# solar_mains_charge_manager.net
KiCad netlist of a schematic drawn in EAGLE
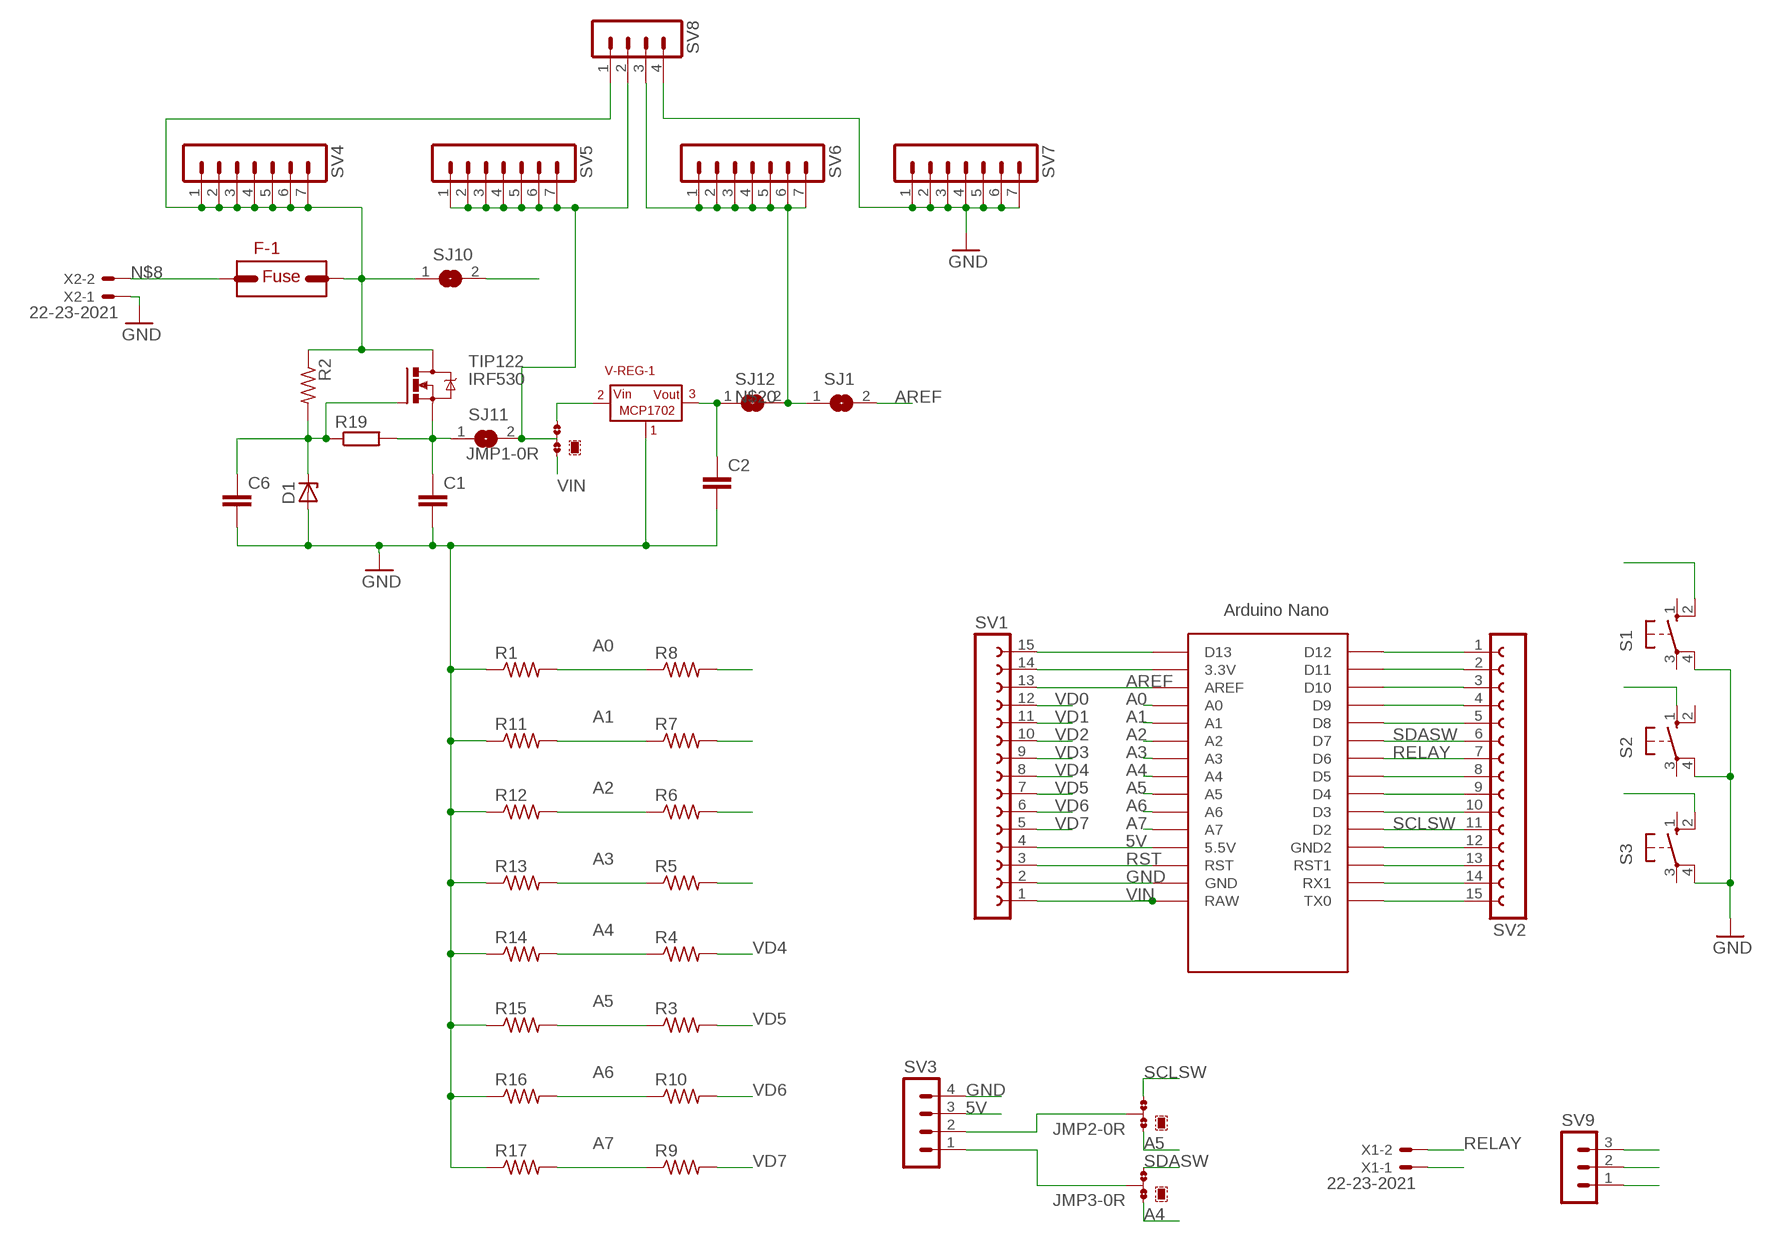
[diagram p0: schematic, sheet 1]

(export (version "E")
  (design (tool "Eeschema 10.0.6"))
  (components
    (comp (ref "C1")
      (value "C2,5-3")
      (footprint "eagle-import:C2.5-3")
      (libsource (lib "eagle-import") (part "C2,5-3"))
    )
    (comp (ref "C2")
      (value "C2,5-3")
      (footprint "eagle-import:C2.5-3")
      (libsource (lib "eagle-import") (part "C2,5-3"))
    )
    (comp (ref "C6")
      (value "C2,5-3")
      (footprint "eagle-import:C2.5-3")
      (libsource (lib "eagle-import") (part "C2,5-3"))
    )
    (comp (ref "D1")
      (value "ZENER-DIODEDO34-7")
      (footprint "eagle-import:DO34Z7")
      (libsource (lib "eagle-import") (part "ZENER-DIODEDO34-7"))
    )
    (comp (ref "F-1")
      (value "FUSE")
      (footprint "eagle-import:FUSE")
      (libsource (lib "eagle-import") (part "FUSE"))
    )
    (comp (ref "JMP1")
      (value "0R-JUMPA")
      (footprint "eagle-import:A0R-JMP")
      (libsource (lib "eagle-import") (part "0R-JUMPA"))
    )
    (comp (ref "JMP2")
      (value "0R-JUMPA")
      (footprint "eagle-import:A0R-JMP")
      (libsource (lib "eagle-import") (part "0R-JUMPA"))
    )
    (comp (ref "JMP3")
      (value "0R-JUMPA")
      (footprint "eagle-import:A0R-JMP")
      (libsource (lib "eagle-import") (part "0R-JUMPA"))
    )
    (comp (ref "R1")
      (value "R-US_0204/5")
      (footprint "eagle-import:0204_5")
      (libsource (lib "eagle-import") (part "R-US_0204/5"))
    )
    (comp (ref "R2")
      (value "R-US_0204/2V")
      (footprint "eagle-import:0204V")
      (libsource (lib "eagle-import") (part "resistor_348_R-US_0204/2V"))
    )
    (comp (ref "R3")
      (value "R-US_0204/2V")
      (footprint "eagle-import:0204V")
      (libsource (lib "eagle-import") (part "resistor_348_R-US_0204/2V"))
    )
    (comp (ref "R4")
      (value "R-US_0204/2V")
      (footprint "eagle-import:0204V")
      (libsource (lib "eagle-import") (part "resistor_348_R-US_0204/2V"))
    )
    (comp (ref "R5")
      (value "R-US_0204/2V")
      (footprint "eagle-import:0204V")
      (libsource (lib "eagle-import") (part "resistor_348_R-US_0204/2V"))
    )
    (comp (ref "R6")
      (value "R-US_0204/2V")
      (footprint "eagle-import:0204V")
      (libsource (lib "eagle-import") (part "resistor_348_R-US_0204/2V"))
    )
    (comp (ref "R7")
      (value "R-US_0204/2V")
      (footprint "eagle-import:0204V")
      (libsource (lib "eagle-import") (part "resistor_348_R-US_0204/2V"))
    )
    (comp (ref "R8")
      (value "R-US_0204/2V")
      (footprint "eagle-import:0204V")
      (libsource (lib "eagle-import") (part "resistor_348_R-US_0204/2V"))
    )
    (comp (ref "R9")
      (value "R-US_0204/2V")
      (footprint "eagle-import:0204V")
      (libsource (lib "eagle-import") (part "resistor_348_R-US_0204/2V"))
    )
    (comp (ref "R10")
      (value "R-US_0204/2V")
      (footprint "eagle-import:0204V")
      (libsource (lib "eagle-import") (part "resistor_348_R-US_0204/2V"))
    )
    (comp (ref "R11")
      (value "R-US_0204/5")
      (footprint "eagle-import:0204_5")
      (libsource (lib "eagle-import") (part "R-US_0204/5"))
    )
    (comp (ref "R12")
      (value "R-US_0204/5")
      (footprint "eagle-import:0204_5")
      (libsource (lib "eagle-import") (part "R-US_0204/5"))
    )
    (comp (ref "R13")
      (value "R-US_0204/5")
      (footprint "eagle-import:0204_5")
      (libsource (lib "eagle-import") (part "R-US_0204/5"))
    )
    (comp (ref "R14")
      (value "R-US_0204/5")
      (footprint "eagle-import:0204_5")
      (libsource (lib "eagle-import") (part "R-US_0204/5"))
    )
    (comp (ref "R15")
      (value "R-US_0204/5")
      (footprint "eagle-import:0204_5")
      (libsource (lib "eagle-import") (part "R-US_0204/5"))
    )
    (comp (ref "R16")
      (value "R-US_0204/5")
      (footprint "eagle-import:0204_5")
      (libsource (lib "eagle-import") (part "R-US_0204/5"))
    )
    (comp (ref "R17")
      (value "R-US_0204/5")
      (footprint "eagle-import:0204_5")
      (libsource (lib "eagle-import") (part "R-US_0204/5"))
    )
    (comp (ref "R19")
      (value "R-EU_0204/5")
      (footprint "eagle-import:0204_5")
      (libsource (lib "eagle-import") (part "R-EU_0204/5"))
    )
    (comp (ref "S1")
      (value "10-XX")
      (footprint "eagle-import:B3F-10XX")
      (fields (field (name "MPN") "B3F-1000"))
      (libsource (lib "eagle-import") (part "10-XX"))
    )
    (comp (ref "S2")
      (value "10-XX")
      (footprint "eagle-import:B3F-10XX")
      (fields (field (name "MPN") "B3F-1000"))
      (libsource (lib "eagle-import") (part "10-XX"))
    )
    (comp (ref "S3")
      (value "10-XX")
      (footprint "eagle-import:B3F-10XX")
      (fields (field (name "MPN") "B3F-1000"))
      (libsource (lib "eagle-import") (part "10-XX"))
    )
    (comp (ref "SJ1") (value "SJ") (footprint "eagle-import:SJ") (libsource (lib "eagle-import") (part "SJ")))
    (comp (ref "SJ10")
      (value "SJ")
      (footprint "eagle-import:SJ")
      (libsource (lib "eagle-import") (part "SJ"))
    )
    (comp (ref "SJ11")
      (value "SJ")
      (footprint "eagle-import:SJ")
      (libsource (lib "eagle-import") (part "SJ"))
    )
    (comp (ref "SJ12")
      (value "SJ")
      (footprint "eagle-import:SJ")
      (libsource (lib "eagle-import") (part "SJ"))
    )
    (comp (ref "SV1")
      (value "FE15-1")
      (footprint "eagle-import:FE15")
      (libsource (lib "eagle-import") (part "FE15-1"))
    )
    (comp (ref "SV2")
      (value "FE15-1")
      (footprint "eagle-import:FE15")
      (libsource (lib "eagle-import") (part "FE15-1"))
    )
    (comp (ref "SV3")
      (value "MA04-1")
      (footprint "eagle-import:MA04-1")
      (libsource (lib "eagle-import") (part "MA04-1"))
    )
    (comp (ref "SV4")
      (value "MA07-1")
      (footprint "eagle-import:MA07-1")
      (libsource (lib "eagle-import") (part "MA07-1"))
    )
    (comp (ref "SV5")
      (value "MA07-1")
      (footprint "eagle-import:MA07-1")
      (libsource (lib "eagle-import") (part "MA07-1"))
    )
    (comp (ref "SV6")
      (value "MA07-1")
      (footprint "eagle-import:MA07-1")
      (libsource (lib "eagle-import") (part "MA07-1"))
    )
    (comp (ref "SV7")
      (value "MA07-1")
      (footprint "eagle-import:MA07-1")
      (libsource (lib "eagle-import") (part "MA07-1"))
    )
    (comp (ref "SV8")
      (value "MA04-1")
      (footprint "eagle-import:MA04-1")
      (libsource (lib "eagle-import") (part "MA04-1"))
    )
    (comp (ref "SV9")
      (value "MA03-1")
      (footprint "eagle-import:MA03-1")
      (libsource (lib "eagle-import") (part "MA03-1"))
    )
    (comp (ref "TIP122")
      (value "IRF530")
      (footprint "eagle-import:TO220BV")
      (libsource (lib "eagle-import") (part "IRF530"))
    )
    (comp (ref "U$1")
      (value "NANO")
      (footprint "eagle-import:NANO")
      (libsource (lib "eagle-import") (part "NANO"))
    )
    (comp (ref "V-REG-1")
      (value "MCP1702")
      (footprint "eagle-import:TO92")
      (libsource (lib "eagle-import") (part "MCP1702"))
    )
    (comp (ref "X1")
      (value "22-23-2021")
      (footprint "eagle-import:22-23-2021")
      (fields (field (name "MF") "MOLEX"))
      (libsource (lib "eagle-import") (part "22-23-2021"))
    )
    (comp (ref "X2")
      (value "22-23-2021")
      (footprint "eagle-import:22-23-2021")
      (fields (field (name "MF") "MOLEX"))
      (libsource (lib "eagle-import") (part "22-23-2021"))
    )
  )
  (nets
    (net (code "1") (name "/5V") (class "Default")
      (node (ref "SJ1") (pin "1") (pinfunction "1_1") (pintype "passive"))
      (node (ref "SJ12") (pin "2") (pinfunction "2_2") (pintype "passive"))
      (node (ref "SV1") (pin "4") (pinfunction "4_4") (pintype "passive"))
      (node (ref "SV3") (pin "3") (pinfunction "3_3") (pintype "passive"))
      (node (ref "SV6") (pin "1") (pinfunction "1_1") (pintype "passive"))
      (node (ref "SV6") (pin "2") (pinfunction "2_2") (pintype "passive"))
      (node (ref "SV6") (pin "3") (pinfunction "3_3") (pintype "passive"))
      (node (ref "SV6") (pin "4") (pinfunction "4_4") (pintype "passive"))
      (node (ref "SV6") (pin "5") (pinfunction "5_5") (pintype "passive"))
      (node (ref "SV6") (pin "6") (pinfunction "6_6") (pintype "passive"))
      (node (ref "SV6") (pin "7") (pinfunction "7_7") (pintype "passive"))
      (node (ref "SV8") (pin "3") (pinfunction "3_3") (pintype "passive"))
      (node (ref "SV9") (pin "3") (pinfunction "3_3") (pintype "passive"))
      (node (ref "U$1") (pin "5V") (pinfunction "5.5V_5V") (pintype "bidirectional"))
    )
    (net (code "2") (name "/A0") (class "Default")
      (node (ref "R1") (pin "2") (pinfunction "2_2") (pintype "passive"))
      (node (ref "R8") (pin "1") (pinfunction "1_1") (pintype "passive"))
      (node (ref "U$1") (pin "A0") (pinfunction "A0_A0") (pintype "bidirectional"))
    )
    (net (code "3") (name "/A1") (class "Default")
      (node (ref "R11") (pin "2") (pinfunction "2_2") (pintype "passive"))
      (node (ref "R7") (pin "1") (pinfunction "1_1") (pintype "passive"))
      (node (ref "U$1") (pin "A1") (pinfunction "A1_A1") (pintype "bidirectional"))
    )
    (net (code "4") (name "/A2") (class "Default")
      (node (ref "R12") (pin "2") (pinfunction "2_2") (pintype "passive"))
      (node (ref "R6") (pin "1") (pinfunction "1_1") (pintype "passive"))
      (node (ref "U$1") (pin "A2") (pinfunction "A2_A2") (pintype "bidirectional"))
    )
    (net (code "5") (name "/A3") (class "Default")
      (node (ref "R13") (pin "2") (pinfunction "2_2") (pintype "passive"))
      (node (ref "R5") (pin "1") (pinfunction "1_1") (pintype "passive"))
      (node (ref "U$1") (pin "A3") (pinfunction "A3_A3") (pintype "bidirectional"))
    )
    (net (code "6") (name "/A4") (class "Default")
      (node (ref "JMP3") (pin "1") (pinfunction "1_1") (pintype "passive"))
      (node (ref "R14") (pin "2") (pinfunction "2_2") (pintype "passive"))
      (node (ref "R4") (pin "1") (pinfunction "1_1") (pintype "passive"))
      (node (ref "U$1") (pin "A4") (pinfunction "A4_A4") (pintype "bidirectional"))
    )
    (net (code "7") (name "/A5") (class "Default")
      (node (ref "JMP2") (pin "1") (pinfunction "1_1") (pintype "passive"))
      (node (ref "R15") (pin "2") (pinfunction "2_2") (pintype "passive"))
      (node (ref "R3") (pin "1") (pinfunction "1_1") (pintype "passive"))
      (node (ref "U$1") (pin "A5") (pinfunction "A5_A5") (pintype "bidirectional"))
    )
    (net (code "8") (name "/A6") (class "Default")
      (node (ref "R10") (pin "1") (pinfunction "1_1") (pintype "passive"))
      (node (ref "R16") (pin "2") (pinfunction "2_2") (pintype "passive"))
      (node (ref "U$1") (pin "A6") (pinfunction "A6_A6") (pintype "bidirectional"))
    )
    (net (code "9") (name "/A7") (class "Default")
      (node (ref "R17") (pin "2") (pinfunction "2_2") (pintype "passive"))
      (node (ref "R9") (pin "1") (pinfunction "1_1") (pintype "passive"))
      (node (ref "SV9") (pin "1") (pinfunction "1_1") (pintype "passive"))
      (node (ref "U$1") (pin "A7") (pinfunction "A7_A7") (pintype "bidirectional"))
    )
    (net (code "10") (name "/AREF") (class "Default")
      (node (ref "SJ1") (pin "2") (pinfunction "2_2") (pintype "passive"))
      (node (ref "SV1") (pin "13") (pinfunction "13_13") (pintype "passive"))
      (node (ref "U$1") (pin "AREF") (pinfunction "AREF_AREF") (pintype "bidirectional"))
    )
    (net (code "11") (name "/D8") (class "Default")
      (node (ref "S2") (pin "1") (pinfunction "S_1") (pintype "passive"))
      (node (ref "SV2") (pin "5") (pinfunction "5_5") (pintype "passive"))
      (node (ref "U$1") (pin "D8") (pinfunction "D8_D8") (pintype "bidirectional"))
    )
    (net (code "12") (name "/D9") (class "Default")
      (node (ref "S1") (pin "2") (pinfunction "S1_2") (pintype "passive"))
      (node (ref "SV2") (pin "4") (pinfunction "4_4") (pintype "passive"))
      (node (ref "U$1") (pin "D9") (pinfunction "D9_D9") (pintype "bidirectional"))
    )
    (net (code "13") (name "/N$8") (class "Default")
      (node (ref "F-1") (pin "P$1") (pinfunction "P$1_P$1") (pintype "passive"))
      (node (ref "X2") (pin "2") (pinfunction "S_2") (pintype "passive"))
    )
    (net (code "14") (name "/N$20") (class "Default")
      (node (ref "C2") (pin "1") (pinfunction "1_1") (pintype "passive"))
      (node (ref "SJ12") (pin "1") (pinfunction "1_1") (pintype "passive"))
      (node (ref "V-REG-1") (pin "3") (pinfunction "P$3_3") (pintype "power_in"))
    )
    (net (code "15") (name "/RELAY") (class "Default")
      (node (ref "SV2") (pin "7") (pinfunction "7_7") (pintype "passive"))
      (node (ref "U$1") (pin "D6") (pinfunction "D6_D6") (pintype "bidirectional"))
      (node (ref "X1") (pin "2") (pinfunction "S_2") (pintype "passive"))
    )
    (net (code "16") (name "/RST") (class "Default")
      (node (ref "S3") (pin "2") (pinfunction "S1_2") (pintype "passive"))
      (node (ref "SV1") (pin "3") (pinfunction "3_3") (pintype "passive"))
      (node (ref "U$1") (pin "RST") (pinfunction "RST_RST") (pintype "bidirectional"))
    )
    (net (code "17") (name "/SCLSW") (class "Default")
      (node (ref "JMP2") (pin "3") (pinfunction "3_3") (pintype "passive"))
      (node (ref "SV2") (pin "11") (pinfunction "11_11") (pintype "passive"))
      (node (ref "U$1") (pin "D2") (pinfunction "D2_D2") (pintype "bidirectional"))
    )
    (net (code "18") (name "/SDASW") (class "Default")
      (node (ref "JMP3") (pin "3") (pinfunction "3_3") (pintype "passive"))
      (node (ref "SV2") (pin "6") (pinfunction "6_6") (pintype "passive"))
      (node (ref "U$1") (pin "D7") (pinfunction "D7_D7") (pintype "bidirectional"))
    )
    (net (code "19") (name "/VD0") (class "Default")
      (node (ref "R8") (pin "2") (pinfunction "2_2") (pintype "passive"))
      (node (ref "SJ10") (pin "2") (pinfunction "2_2") (pintype "passive"))
      (node (ref "SV1") (pin "12") (pinfunction "12_12") (pintype "passive"))
    )
    (net (code "20") (name "/VD1") (class "Default")
      (node (ref "R7") (pin "2") (pinfunction "2_2") (pintype "passive"))
      (node (ref "SV1") (pin "11") (pinfunction "11_11") (pintype "passive"))
    )
    (net (code "21") (name "/VD2") (class "Default")
      (node (ref "R6") (pin "2") (pinfunction "2_2") (pintype "passive"))
      (node (ref "SV1") (pin "10") (pinfunction "10_10") (pintype "passive"))
    )
    (net (code "22") (name "/VD3") (class "Default")
      (node (ref "R5") (pin "2") (pinfunction "2_2") (pintype "passive"))
      (node (ref "SV1") (pin "9") (pinfunction "9_9") (pintype "passive"))
    )
    (net (code "23") (name "/VD4") (class "Default")
      (node (ref "R4") (pin "2") (pinfunction "2_2") (pintype "passive"))
      (node (ref "SV1") (pin "8") (pinfunction "8_8") (pintype "passive"))
    )
    (net (code "24") (name "/VD5") (class "Default")
      (node (ref "R3") (pin "2") (pinfunction "2_2") (pintype "passive"))
      (node (ref "SV1") (pin "7") (pinfunction "7_7") (pintype "passive"))
    )
    (net (code "25") (name "/VD6") (class "Default")
      (node (ref "R10") (pin "2") (pinfunction "2_2") (pintype "passive"))
      (node (ref "SV1") (pin "6") (pinfunction "6_6") (pintype "passive"))
    )
    (net (code "26") (name "/VD7") (class "Default")
      (node (ref "R9") (pin "2") (pinfunction "2_2") (pintype "passive"))
      (node (ref "SV1") (pin "5") (pinfunction "5_5") (pintype "passive"))
    )
    (net (code "27") (name "/VIN") (class "Default")
      (node (ref "JMP1") (pin "1") (pinfunction "1_1") (pintype "passive"))
      (node (ref "SV1") (pin "1") (pinfunction "1_1") (pintype "passive"))
      (node (ref "U$1") (pin "RAW") (pinfunction "RAW_RAW") (pintype "bidirectional"))
    )
    (net (code "28") (name "GND") (class "Default")
      (node (ref "C1") (pin "2") (pinfunction "2_2") (pintype "passive"))
      (node (ref "C2") (pin "2") (pinfunction "2_2") (pintype "passive"))
      (node (ref "C6") (pin "2") (pinfunction "2_2") (pintype "passive"))
      (node (ref "D1") (pin "A") (pinfunction "A_A") (pintype "passive"))
      (node (ref "R1") (pin "1") (pinfunction "1_1") (pintype "passive"))
      (node (ref "R11") (pin "1") (pinfunction "1_1") (pintype "passive"))
      (node (ref "R12") (pin "1") (pinfunction "1_1") (pintype "passive"))
      (node (ref "R13") (pin "1") (pinfunction "1_1") (pintype "passive"))
      (node (ref "R14") (pin "1") (pinfunction "1_1") (pintype "passive"))
      (node (ref "R15") (pin "1") (pinfunction "1_1") (pintype "passive"))
      (node (ref "R16") (pin "1") (pinfunction "1_1") (pintype "passive"))
      (node (ref "R17") (pin "1") (pinfunction "1_1") (pintype "passive"))
      (node (ref "S1") (pin "4") (pinfunction "P1_4") (pintype "passive"))
      (node (ref "S2") (pin "4") (pinfunction "P1_4") (pintype "passive"))
      (node (ref "S3") (pin "4") (pinfunction "P1_4") (pintype "passive"))
      (node (ref "SV1") (pin "2") (pinfunction "2_2") (pintype "passive"))
      (node (ref "SV2") (pin "12") (pinfunction "12_12") (pintype "passive"))
      (node (ref "SV3") (pin "4") (pinfunction "4_4") (pintype "passive"))
      (node (ref "SV7") (pin "1") (pinfunction "1_1") (pintype "passive"))
      (node (ref "SV7") (pin "2") (pinfunction "2_2") (pintype "passive"))
      (node (ref "SV7") (pin "3") (pinfunction "3_3") (pintype "passive"))
      (node (ref "SV7") (pin "4") (pinfunction "4_4") (pintype "passive"))
      (node (ref "SV7") (pin "5") (pinfunction "5_5") (pintype "passive"))
      (node (ref "SV7") (pin "6") (pinfunction "6_6") (pintype "passive"))
      (node (ref "SV7") (pin "7") (pinfunction "7_7") (pintype "passive"))
      (node (ref "SV8") (pin "4") (pinfunction "4_4") (pintype "passive"))
      (node (ref "SV9") (pin "2") (pinfunction "2_2") (pintype "passive"))
      (node (ref "U$1") (pin "GND") (pinfunction "GND_GND") (pintype "bidirectional"))
      (node (ref "U$1") (pin "GND1") (pinfunction "GND2_GND1") (pintype "bidirectional"))
      (node (ref "V-REG-1") (pin "1") (pinfunction "P$2_1") (pintype "power_in"))
      (node (ref "X1") (pin "1") (pinfunction "S_1") (pintype "passive"))
      (node (ref "X2") (pin "1") (pinfunction "S_1") (pintype "passive"))
    )
    (net (code "29") (name "Net-(C1-Pad1)") (class "Default")
      (node (ref "C1") (pin "1") (pinfunction "1_1") (pintype "passive"))
      (node (ref "R19") (pin "2") (pinfunction "2_2") (pintype "passive"))
      (node (ref "SJ11") (pin "1") (pinfunction "1_1") (pintype "passive"))
      (node (ref "TIP122") (pin "S") (pinfunction "S_S") (pintype "passive"))
    )
    (net (code "30") (name "Net-(C6-Pad1)") (class "Default")
      (node (ref "C6") (pin "1") (pinfunction "1_1") (pintype "passive"))
      (node (ref "D1") (pin "C") (pinfunction "C_C") (pintype "passive"))
      (node (ref "R19") (pin "1") (pinfunction "1_1") (pintype "passive"))
      (node (ref "R2") (pin "2") (pinfunction "2_2") (pintype "passive"))
      (node (ref "TIP122") (pin "G") (pinfunction "G_G") (pintype "passive"))
    )
    (net (code "31") (name "Net-(F-1-PadP$2)") (class "Default")
      (node (ref "F-1") (pin "P$2") (pinfunction "P$2_P$2") (pintype "passive"))
      (node (ref "R2") (pin "1") (pinfunction "1_1") (pintype "passive"))
      (node (ref "SJ10") (pin "1") (pinfunction "1_1") (pintype "passive"))
      (node (ref "SV4") (pin "1") (pinfunction "1_1") (pintype "passive"))
      (node (ref "SV4") (pin "2") (pinfunction "2_2") (pintype "passive"))
      (node (ref "SV4") (pin "3") (pinfunction "3_3") (pintype "passive"))
      (node (ref "SV4") (pin "4") (pinfunction "4_4") (pintype "passive"))
      (node (ref "SV4") (pin "5") (pinfunction "5_5") (pintype "passive"))
      (node (ref "SV4") (pin "6") (pinfunction "6_6") (pintype "passive"))
      (node (ref "SV4") (pin "7") (pinfunction "7_7") (pintype "passive"))
      (node (ref "SV8") (pin "1") (pinfunction "1_1") (pintype "passive"))
      (node (ref "TIP122") (pin "D") (pinfunction "D_D") (pintype "passive"))
    )
    (net (code "32") (name "Net-(JMP1-Pad2)") (class "Default")
      (node (ref "JMP1") (pin "2") (pinfunction "2_2") (pintype "passive"))
      (node (ref "SJ11") (pin "2") (pinfunction "2_2") (pintype "passive"))
      (node (ref "SV5") (pin "1") (pinfunction "1_1") (pintype "passive"))
      (node (ref "SV5") (pin "2") (pinfunction "2_2") (pintype "passive"))
      (node (ref "SV5") (pin "3") (pinfunction "3_3") (pintype "passive"))
      (node (ref "SV5") (pin "4") (pinfunction "4_4") (pintype "passive"))
      (node (ref "SV5") (pin "5") (pinfunction "5_5") (pintype "passive"))
      (node (ref "SV5") (pin "6") (pinfunction "6_6") (pintype "passive"))
      (node (ref "SV5") (pin "7") (pinfunction "7_7") (pintype "passive"))
      (node (ref "SV8") (pin "2") (pinfunction "2_2") (pintype "passive"))
    )
    (net (code "33") (name "Net-(JMP2-Pad2)") (class "Default")
      (node (ref "JMP2") (pin "2") (pinfunction "2_2") (pintype "passive"))
      (node (ref "SV3") (pin "2") (pinfunction "2_2") (pintype "passive"))
    )
    (net (code "34") (name "Net-(JMP3-Pad2)") (class "Default")
      (node (ref "JMP3") (pin "2") (pinfunction "2_2") (pintype "passive"))
      (node (ref "SV3") (pin "1") (pinfunction "1_1") (pintype "passive"))
    )
    (net (code "35") (name "Net-(SV1-Pad14)") (class "Default")
      (node (ref "SV1") (pin "14") (pinfunction "14_14") (pintype "passive"))
      (node (ref "U$1") (pin "3.3V") (pinfunction "3.3V_3.3V") (pintype "bidirectional"))
    )
    (net (code "36") (name "Net-(SV1-Pad15)") (class "Default")
      (node (ref "SV1") (pin "15") (pinfunction "15_15") (pintype "passive"))
      (node (ref "U$1") (pin "D13") (pinfunction "D13_D13") (pintype "bidirectional"))
    )
    (net (code "37") (name "Net-(SV2-Pad1)") (class "Default")
      (node (ref "SV2") (pin "1") (pinfunction "1_1") (pintype "passive"))
      (node (ref "U$1") (pin "D12") (pinfunction "D12_D12") (pintype "bidirectional"))
    )
    (net (code "38") (name "Net-(SV2-Pad2)") (class "Default")
      (node (ref "SV2") (pin "2") (pinfunction "2_2") (pintype "passive"))
      (node (ref "U$1") (pin "D11") (pinfunction "D11_D11") (pintype "bidirectional"))
    )
    (net (code "39") (name "Net-(SV2-Pad3)") (class "Default")
      (node (ref "SV2") (pin "3") (pinfunction "3_3") (pintype "passive"))
      (node (ref "U$1") (pin "D10") (pinfunction "D10_D10") (pintype "bidirectional"))
    )
    (net (code "40") (name "Net-(SV2-Pad8)") (class "Default")
      (node (ref "SV2") (pin "8") (pinfunction "8_8") (pintype "passive"))
      (node (ref "U$1") (pin "D5") (pinfunction "D5_D5") (pintype "bidirectional"))
    )
    (net (code "41") (name "Net-(SV2-Pad9)") (class "Default")
      (node (ref "SV2") (pin "9") (pinfunction "9_9") (pintype "passive"))
      (node (ref "U$1") (pin "D4") (pinfunction "D4_D4") (pintype "bidirectional"))
    )
    (net (code "42") (name "Net-(SV2-Pad10)") (class "Default")
      (node (ref "SV2") (pin "10") (pinfunction "10_10") (pintype "passive"))
      (node (ref "U$1") (pin "D3") (pinfunction "D3_D3") (pintype "bidirectional"))
    )
    (net (code "43") (name "Net-(SV2-Pad13)") (class "Default")
      (node (ref "SV2") (pin "13") (pinfunction "13_13") (pintype "passive"))
      (node (ref "U$1") (pin "RST1") (pinfunction "RST1_RST1") (pintype "bidirectional"))
    )
    (net (code "44") (name "Net-(SV2-Pad14)") (class "Default")
      (node (ref "SV2") (pin "14") (pinfunction "14_14") (pintype "passive"))
      (node (ref "U$1") (pin "RX1") (pinfunction "RX1_RX1") (pintype "bidirectional"))
    )
    (net (code "45") (name "Net-(SV2-Pad15)") (class "Default")
      (node (ref "SV2") (pin "15") (pinfunction "15_15") (pintype "passive"))
      (node (ref "U$1") (pin "TX0") (pinfunction "TX0_TX0") (pintype "bidirectional"))
    )
    (net (code "46") (name "Net-(V-REG-1-P$1)") (class "Default")
      (node (ref "JMP1") (pin "3") (pinfunction "3_3") (pintype "passive"))
      (node (ref "V-REG-1") (pin "2") (pinfunction "P$1_2") (pintype "power_in"))
    )
    (net (code "47") (name "unconnected-(S1-P-Pad3)") (class "Default")
      (node (ref "S1") (pin "3") (pinfunction "P_3") (pintype "passive"))
    )
    (net (code "48") (name "unconnected-(S1-S-Pad1)") (class "Default")
      (node (ref "S1") (pin "1") (pinfunction "S_1") (pintype "passive"))
    )
    (net (code "49") (name "unconnected-(S2-P-Pad3)") (class "Default")
      (node (ref "S2") (pin "3") (pinfunction "P_3") (pintype "passive"))
    )
    (net (code "50") (name "unconnected-(S2-S1-Pad2)") (class "Default")
      (node (ref "S2") (pin "2") (pinfunction "S1_2") (pintype "passive"))
    )
    (net (code "51") (name "unconnected-(S3-P-Pad3)") (class "Default")
      (node (ref "S3") (pin "3") (pinfunction "P_3") (pintype "passive"))
    )
    (net (code "52") (name "unconnected-(S3-S-Pad1)") (class "Default")
      (node (ref "S3") (pin "1") (pinfunction "S_1") (pintype "passive"))
    )
  )
)
